# UNO_florist_automata_V1_10.net
KiCad netlist of a schematic drawn in EAGLE
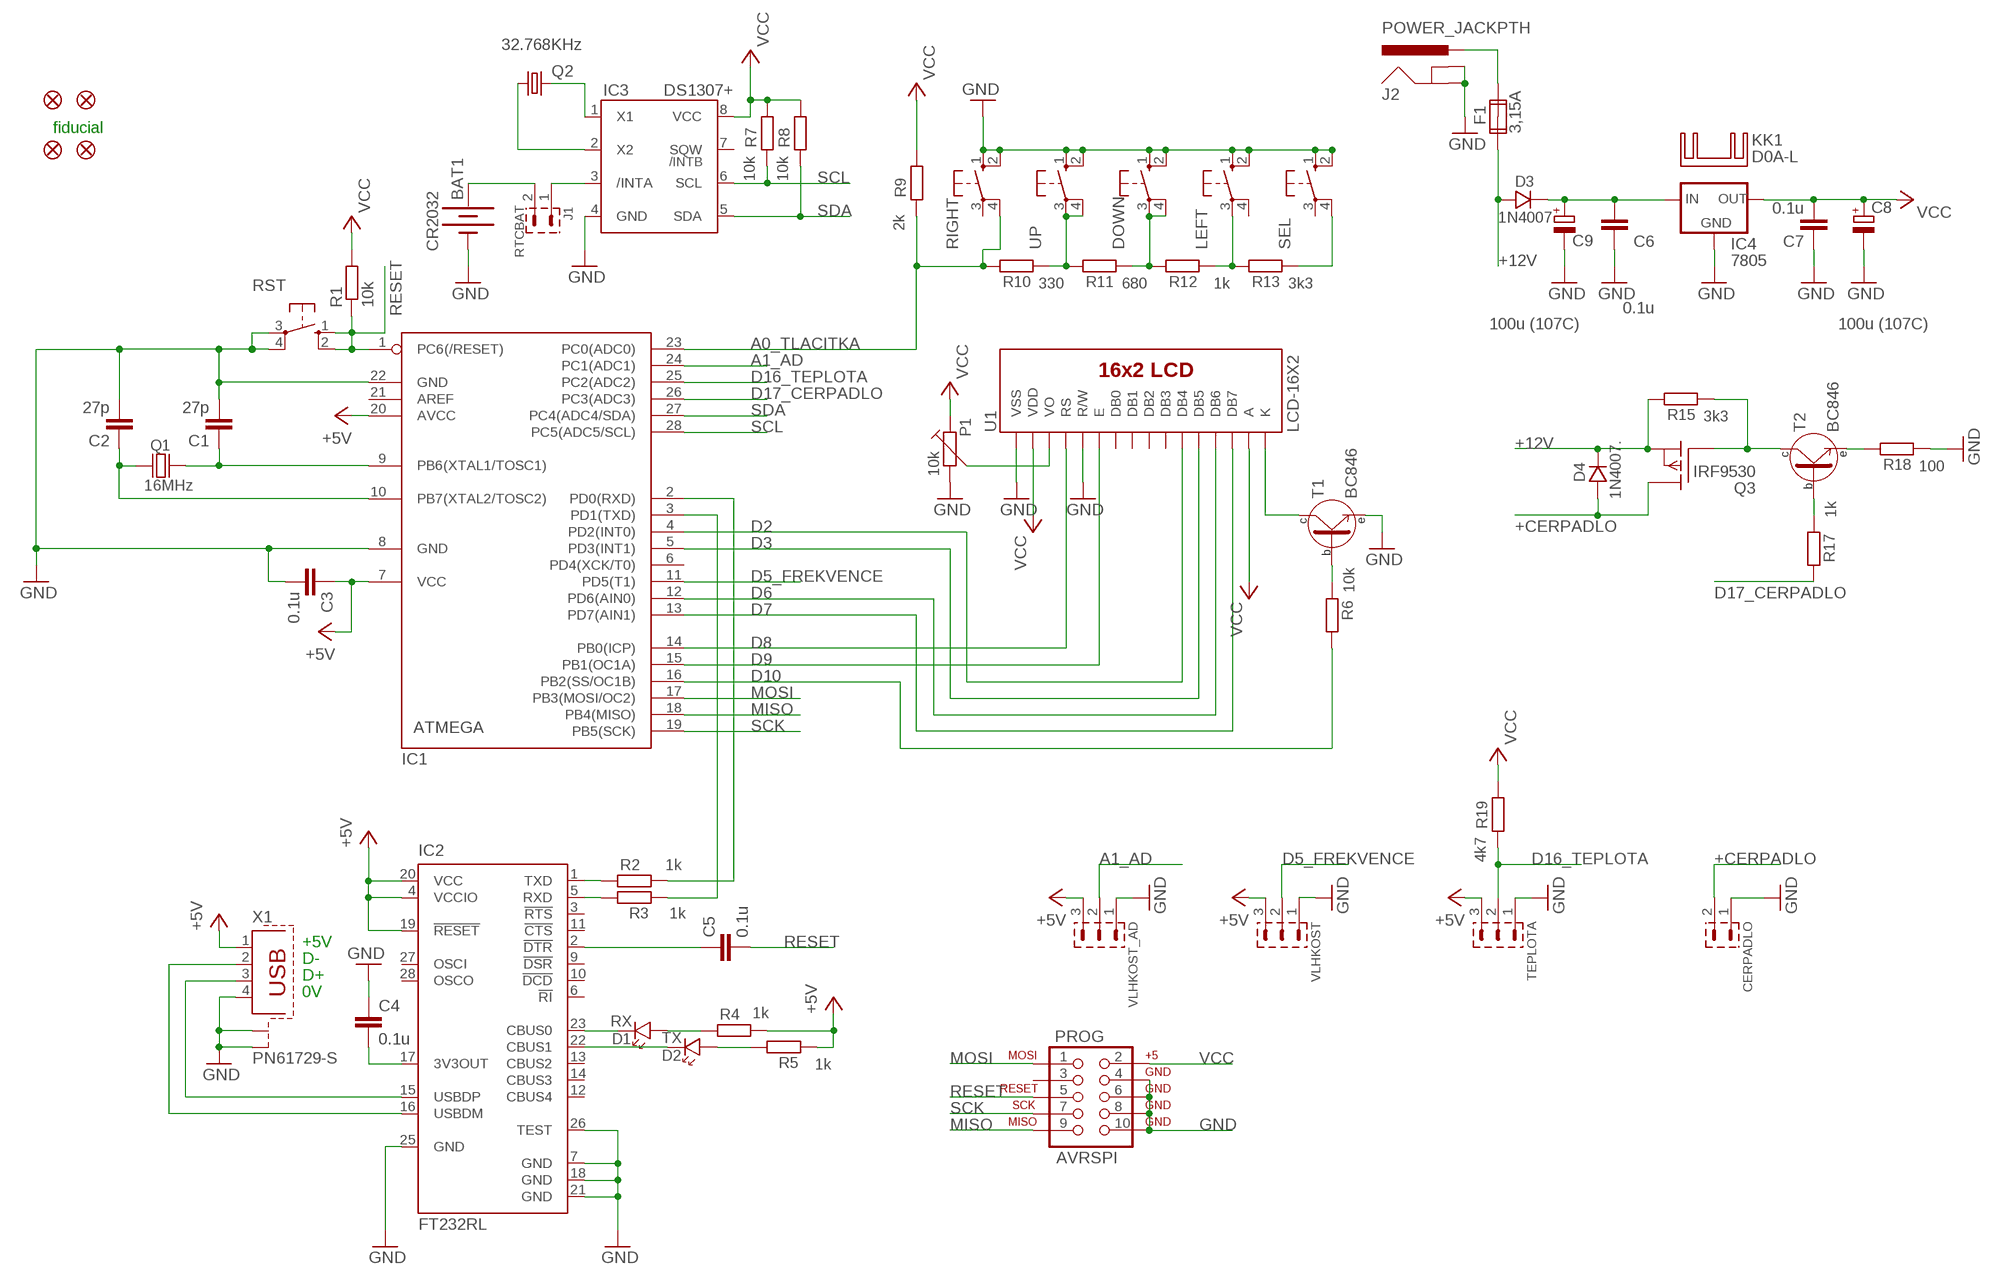
[diagram p0: schematic, sheet 1]

(export (version "E")
  (design (tool "Eeschema 10.0.6"))
  (components
    (comp (ref "BAT1")
      (value "CR2032")
      (footprint "eagle-import:BATTCOM_20MM_PTH")
      (libsource (lib "eagle-import") (part "BATTERY20PTH"))
    )
    (comp (ref "C1")
      (value "27p")
      (footprint "eagle-import:C1206")
      (libsource (lib "eagle-import") (part "C-EUC1206"))
    )
    (comp (ref "C2")
      (value "27p")
      (footprint "eagle-import:C1206")
      (libsource (lib "eagle-import") (part "C-EUC1206"))
    )
    (comp (ref "C3")
      (value "0.1u")
      (footprint "eagle-import:C1206")
      (libsource (lib "eagle-import") (part "C-EUC1206"))
    )
    (comp (ref "C4")
      (value "0.1u")
      (footprint "eagle-import:C1206")
      (libsource (lib "eagle-import") (part "C-EUC1206"))
    )
    (comp (ref "C5")
      (value "0.1u")
      (footprint "eagle-import:C1206")
      (libsource (lib "eagle-import") (part "C-EUC1206"))
    )
    (comp (ref "C6")
      (value "0.1u")
      (footprint "eagle-import:C1206")
      (libsource (lib "eagle-import") (part "C-EUC1206"))
    )
    (comp (ref "C7")
      (value "0.1u")
      (footprint "eagle-import:C1206")
      (libsource (lib "eagle-import") (part "C-EUC1206"))
    )
    (comp (ref "C8")
      (value "100u (107C)")
      (footprint "eagle-import:C_6032-28W")
      (libsource (lib "eagle-import") (part "CPOL-EUC/6032-28W"))
    )
    (comp (ref "C9")
      (value "100u (107C)")
      (footprint "eagle-import:C_6032-28W")
      (libsource (lib "eagle-import") (part "CPOL-EUC/6032-28W"))
    )
    (comp (ref "CERPADLO")
      (value "PSH02-02P")
      (footprint "eagle-import:PSH02-02P")
      (libsource (lib "eagle-import") (part "PSH02-02P"))
    )
    (comp (ref "D1")
      (value "RX")
      (footprint "eagle-import:P1206")
      (libsource (lib "eagle-import") (part "LED_1206"))
    )
    (comp (ref "D2")
      (value "TX")
      (footprint "eagle-import:P1206")
      (libsource (lib "eagle-import") (part "LED_1206"))
    )
    (comp (ref "D3")
      (value "1N4007.")
      (footprint "eagle-import:SM-1")
      (libsource (lib "eagle-import") (part "1N4007."))
    )
    (comp (ref "D4")
      (value "1N4007.")
      (footprint "eagle-import:SM-1")
      (libsource (lib "eagle-import") (part "1N4007."))
    )
    (comp (ref "DOWN")
      (value "10-XX")
      (footprint "eagle-import:B3F-10XX")
      (libsource (lib "eagle-import") (part "10-XX"))
    )
    (comp (ref "F1")
      (value "3,15A")
      (footprint "eagle-import:FUSE1")
      (libsource (lib "eagle-import") (part "FUSE2P"))
    )
    (comp (ref "FID1")
      (value "FIDUCIAL1.5X3")
      (footprint "eagle-import:FIDUCIAL-1.5X3")
      (libsource (lib "eagle-import") (part "FIDUCIAL1.5X3"))
    )
    (comp (ref "FID2")
      (value "FIDUCIAL1.5X3")
      (footprint "eagle-import:FIDUCIAL-1.5X3")
      (libsource (lib "eagle-import") (part "FIDUCIAL1.5X3"))
    )
    (comp (ref "FID3")
      (value "FIDUCIAL1.5X3")
      (footprint "eagle-import:FIDUCIAL-1.5X3")
      (libsource (lib "eagle-import") (part "FIDUCIAL1.5X3"))
    )
    (comp (ref "FID4")
      (value "FIDUCIAL1.5X3")
      (footprint "eagle-import:FIDUCIAL-1.5X3")
      (libsource (lib "eagle-import") (part "FIDUCIAL1.5X3"))
    )
    (comp (ref "IC1")
      (value "ATMEGA")
      (footprint "eagle-import:DIL28-3")
      (libsource (lib "eagle-import") (part "MEGA8-P"))
    )
    (comp (ref "IC2")
      (value "FT232RL")
      (footprint "eagle-import:SSOP28")
      (libsource (lib "eagle-import") (part "FT232RL"))
    )
    (comp (ref "IC3")
      (value "DS1307+")
      (footprint "eagle-import:SO08")
      (libsource (lib "eagle-import") (part "DS1337S+"))
    )
    (comp (ref "IC4")
      (value "7805")
      (footprint "eagle-import:78XXL")
      (libsource (lib "eagle-import") (part "78XXL"))
    )
    (comp (ref "J1")
      (value "RTCBAT")
      (footprint "eagle-import:S1G2_JUM")
      (libsource (lib "eagle-import") (part "S1G2_JUMP"))
    )
    (comp (ref "J2")
      (value "POWER_JACKPTH")
      (footprint "eagle-import:POWER_JACK_PTH")
      (libsource (lib "eagle-import") (part "POWER_JACKPTH"))
    )
    (comp (ref "KK1")
      (value "D0A-L")
      (footprint "eagle-import:D02A-L")
      (libsource (lib "eagle-import") (part "D0A-L"))
    )
    (comp (ref "LEFT")
      (value "10-XX")
      (footprint "eagle-import:B3F-10XX")
      (libsource (lib "eagle-import") (part "10-XX"))
    )
    (comp (ref "P1")
      (value "10k")
      (footprint "eagle-import:PT10V")
      (libsource (lib "eagle-import") (part "TRIMRPT10V"))
    )
    (comp (ref "PROG")
      (value "AVRSPI")
      (footprint "eagle-import:2X5-SHROUDED_LOCK")
      (libsource (lib "eagle-import") (part "AVR_SPI_PROG2LOCK"))
    )
    (comp (ref "Q1")
      (value "16MHz")
      (footprint "eagle-import:HC-49U")
      (libsource (lib "eagle-import") (part "Q_HC-49U"))
    )
    (comp (ref "Q2")
      (value "32.768KHz")
      (footprint "eagle-import:TC38H")
      (libsource (lib "eagle-import") (part "CRYSTALTC38H"))
    )
    (comp (ref "Q3")
      (value "IRF9530")
      (footprint "eagle-import:TO220")
      (libsource (lib "eagle-import") (part "IRF9530"))
    )
    (comp (ref "R1")
      (value "10k")
      (footprint "eagle-import:M1206")
      (libsource (lib "eagle-import") (part "R-EU_M1206"))
    )
    (comp (ref "R2")
      (value "1k")
      (footprint "eagle-import:M1206")
      (libsource (lib "eagle-import") (part "R-EU_M1206"))
    )
    (comp (ref "R3")
      (value "1k")
      (footprint "eagle-import:M1206")
      (libsource (lib "eagle-import") (part "R-EU_M1206"))
    )
    (comp (ref "R4")
      (value "1k")
      (footprint "eagle-import:M1206")
      (libsource (lib "eagle-import") (part "R-EU_M1206"))
    )
    (comp (ref "R5")
      (value "1k")
      (footprint "eagle-import:M1206")
      (libsource (lib "eagle-import") (part "R-EU_M1206"))
    )
    (comp (ref "R6")
      (value "10k")
      (footprint "eagle-import:M1206")
      (libsource (lib "eagle-import") (part "R-EU_M1206"))
    )
    (comp (ref "R7")
      (value "10k")
      (footprint "eagle-import:M1206")
      (libsource (lib "eagle-import") (part "R-EU_M1206"))
    )
    (comp (ref "R8")
      (value "10k")
      (footprint "eagle-import:M1206")
      (libsource (lib "eagle-import") (part "R-EU_M1206"))
    )
    (comp (ref "R9")
      (value "2k")
      (footprint "eagle-import:M1206")
      (libsource (lib "eagle-import") (part "R-EU_M1206"))
    )
    (comp (ref "R10")
      (value "330")
      (footprint "eagle-import:M1206")
      (libsource (lib "eagle-import") (part "R-EU_M1206"))
    )
    (comp (ref "R11")
      (value "680")
      (footprint "eagle-import:M1206")
      (libsource (lib "eagle-import") (part "R-EU_M1206"))
    )
    (comp (ref "R12")
      (value "1k")
      (footprint "eagle-import:M1206")
      (libsource (lib "eagle-import") (part "R-EU_M1206"))
    )
    (comp (ref "R13")
      (value "3k3")
      (footprint "eagle-import:M1206")
      (libsource (lib "eagle-import") (part "R-EU_M1206"))
    )
    (comp (ref "R15")
      (value "3k3")
      (footprint "eagle-import:M1206")
      (libsource (lib "eagle-import") (part "R-EU_M1206"))
    )
    (comp (ref "R17")
      (value "1k")
      (footprint "eagle-import:M1206")
      (libsource (lib "eagle-import") (part "R-EU_M1206"))
    )
    (comp (ref "R18")
      (value "100")
      (footprint "eagle-import:M1206")
      (libsource (lib "eagle-import") (part "R-EU_M1206"))
    )
    (comp (ref "R19")
      (value "4k7")
      (footprint "eagle-import:M1206")
      (libsource (lib "eagle-import") (part "R-EU_M1206"))
    )
    (comp (ref "RIGHT")
      (value "10-XX")
      (footprint "eagle-import:B3F-10XX")
      (libsource (lib "eagle-import") (part "10-XX"))
    )
    (comp (ref "RST")
      (value "10-XX")
      (footprint "eagle-import:B3F-10XX")
      (libsource (lib "eagle-import") (part "10-XX"))
    )
    (comp (ref "SEL")
      (value "10-XX")
      (footprint "eagle-import:B3F-10XX")
      (libsource (lib "eagle-import") (part "10-XX"))
    )
    (comp (ref "T1")
      (value "BC846")
      (footprint "eagle-import:SOT-23")
      (libsource (lib "eagle-import") (part "BC846"))
    )
    (comp (ref "T2")
      (value "BC846")
      (footprint "eagle-import:SOT-23")
      (libsource (lib "eagle-import") (part "BC846"))
    )
    (comp (ref "TEPLOTA")
      (value "PSH02-03P")
      (footprint "eagle-import:PSH02-03P")
      (libsource (lib "eagle-import") (part "PSH02-03P"))
    )
    (comp (ref "U1")
      (value "LCD-16X2")
      (footprint "eagle-import:LCD-16X2_NOSILK")
      (libsource (lib "eagle-import") (part "LCD-16X2NOSILK"))
    )
    (comp (ref "UP")
      (value "10-XX")
      (footprint "eagle-import:B3F-10XX")
      (libsource (lib "eagle-import") (part "10-XX"))
    )
    (comp (ref "VLHKOST")
      (value "PSH02-03P")
      (footprint "eagle-import:PSH02-03P")
      (libsource (lib "eagle-import") (part "PSH02-03P"))
    )
    (comp (ref "VLHKOST_AD")
      (value "PSH02-03P")
      (footprint "eagle-import:PSH02-03P")
      (libsource (lib "eagle-import") (part "PSH02-03P"))
    )
    (comp (ref "X1")
      (value "PN61729-S")
      (footprint "eagle-import:PN61729-S")
      (libsource (lib "eagle-import") (part "PN61729-S"))
    )
  )
  (nets
    (net (code "1") (name "+5V") (class "Default")
      (node (ref "C3") (pin "1") (pinfunction "1_1") (pintype "passive"))
      (node (ref "C7") (pin "2") (pinfunction "2_2") (pintype "passive"))
      (node (ref "C8") (pin "+") (pinfunction "+_+") (pintype "passive"))
      (node (ref "IC1") (pin "20") (pinfunction "AVCC_20") (pintype "power_in"))
      (node (ref "IC1") (pin "7") (pinfunction "VCC_7") (pintype "power_in"))
      (node (ref "IC2") (pin "19") (pinfunction "~{RESET}_19") (pintype "input"))
      (node (ref "IC2") (pin "20") (pinfunction "VCC_20") (pintype "power_in"))
      (node (ref "IC2") (pin "4") (pinfunction "VCCIO_4") (pintype "power_in"))
      (node (ref "IC3") (pin "8") (pinfunction "VCC_8") (pintype "power_in"))
      (node (ref "IC4") (pin "OUT") (pinfunction "OUT_OUT") (pintype "passive"))
      (node (ref "P1") (pin "1") (pinfunction "1_1") (pintype "passive"))
      (node (ref "PROG") (pin "2") (pinfunction "2_2") (pintype "passive"))
      (node (ref "R1") (pin "2") (pinfunction "2_2") (pintype "passive"))
      (node (ref "R19") (pin "2") (pinfunction "2_2") (pintype "passive"))
      (node (ref "R4") (pin "2") (pinfunction "2_2") (pintype "passive"))
      (node (ref "R5") (pin "1") (pinfunction "1_1") (pintype "passive"))
      (node (ref "R7") (pin "2") (pinfunction "2_2") (pintype "passive"))
      (node (ref "R8") (pin "2") (pinfunction "2_2") (pintype "passive"))
      (node (ref "R9") (pin "2") (pinfunction "2_2") (pintype "passive"))
      (node (ref "TEPLOTA") (pin "3") (pinfunction "3_3") (pintype "passive"))
      (node (ref "U1") (pin "15") (pinfunction "A_15") (pintype "power_in"))
      (node (ref "U1") (pin "2") (pinfunction "VDD_2") (pintype "power_in"))
      (node (ref "VLHKOST") (pin "3") (pinfunction "3_3") (pintype "passive"))
      (node (ref "VLHKOST_AD") (pin "3") (pinfunction "3_3") (pintype "passive"))
      (node (ref "X1") (pin "1") (pinfunction "1_1") (pintype "passive"))
    )
    (net (code "2") (name "/+12V") (class "Default")
      (node (ref "D3") (pin "A") (pinfunction "A_A") (pintype "passive"))
      (node (ref "D4") (pin "K") (pinfunction "K_K") (pintype "passive"))
      (node (ref "F1") (pin "1A") (pinfunction "1A_1A") (pintype "passive"))
      (node (ref "Q3") (pin "3") (pinfunction "S_3") (pintype "passive"))
      (node (ref "R15") (pin "2") (pinfunction "2_2") (pintype "passive"))
    )
    (net (code "3") (name "/+CERPADLO") (class "Default")
      (node (ref "CERPADLO") (pin "2") (pinfunction "2_2") (pintype "passive"))
      (node (ref "D4") (pin "A") (pinfunction "A_A") (pintype "passive"))
      (node (ref "Q3") (pin "2") (pinfunction "D_2") (pintype "passive"))
    )
    (net (code "4") (name "/A0_TLACITKA") (class "Default")
      (node (ref "IC1") (pin "23") (pinfunction "PC0(ADC0)_23") (pintype "bidirectional"))
      (node (ref "R10") (pin "2") (pinfunction "2_2") (pintype "passive"))
      (node (ref "R9") (pin "1") (pinfunction "1_1") (pintype "passive"))
      (node (ref "RIGHT") (pin "4") (pinfunction "P1_4") (pintype "passive"))
    )
    (net (code "5") (name "/A1_AD") (class "Default")
      (node (ref "IC1") (pin "24") (pinfunction "PC1(ADC1)_24") (pintype "bidirectional"))
      (node (ref "VLHKOST_AD") (pin "2") (pinfunction "2_2") (pintype "passive"))
    )
    (net (code "6") (name "/D2") (class "Default")
      (node (ref "IC1") (pin "4") (pinfunction "PD2(INT0)_4") (pintype "bidirectional"))
      (node (ref "U1") (pin "11") (pinfunction "DB4_11") (pintype "bidirectional"))
    )
    (net (code "7") (name "/D3") (class "Default")
      (node (ref "IC1") (pin "5") (pinfunction "PD3(INT1)_5") (pintype "bidirectional"))
      (node (ref "U1") (pin "12") (pinfunction "DB5_12") (pintype "bidirectional"))
    )
    (net (code "8") (name "/D5_FREKVENCE") (class "Default")
      (node (ref "IC1") (pin "11") (pinfunction "PD5(T1)_11") (pintype "bidirectional"))
      (node (ref "VLHKOST") (pin "2") (pinfunction "2_2") (pintype "passive"))
    )
    (net (code "9") (name "/D6") (class "Default")
      (node (ref "IC1") (pin "12") (pinfunction "PD6(AIN0)_12") (pintype "bidirectional"))
      (node (ref "U1") (pin "13") (pinfunction "DB6_13") (pintype "bidirectional"))
    )
    (net (code "10") (name "/D7") (class "Default")
      (node (ref "IC1") (pin "13") (pinfunction "PD7(AIN1)_13") (pintype "bidirectional"))
      (node (ref "U1") (pin "14") (pinfunction "DB7_14") (pintype "bidirectional"))
    )
    (net (code "11") (name "/D8") (class "Default")
      (node (ref "IC1") (pin "14") (pinfunction "PB0(ICP)_14") (pintype "bidirectional"))
      (node (ref "U1") (pin "4") (pinfunction "RS_4") (pintype "input"))
    )
    (net (code "12") (name "/D9") (class "Default")
      (node (ref "IC1") (pin "15") (pinfunction "PB1(OC1A)_15") (pintype "bidirectional"))
      (node (ref "U1") (pin "6") (pinfunction "E_6") (pintype "input"))
    )
    (net (code "13") (name "/D10") (class "Default")
      (node (ref "IC1") (pin "16") (pinfunction "PB2(SS/OC1B)_16") (pintype "bidirectional"))
      (node (ref "R6") (pin "2") (pinfunction "2_2") (pintype "passive"))
    )
    (net (code "14") (name "/D16_TEPLOTA") (class "Default")
      (node (ref "IC1") (pin "25") (pinfunction "PC2(ADC2)_25") (pintype "bidirectional"))
      (node (ref "R19") (pin "1") (pinfunction "1_1") (pintype "passive"))
      (node (ref "TEPLOTA") (pin "2") (pinfunction "2_2") (pintype "passive"))
    )
    (net (code "15") (name "/D17_CERPADLO") (class "Default")
      (node (ref "IC1") (pin "26") (pinfunction "PC3(ADC3)_26") (pintype "bidirectional"))
      (node (ref "R17") (pin "2") (pinfunction "2_2") (pintype "passive"))
    )
    (net (code "16") (name "/MISO") (class "Default")
      (node (ref "IC1") (pin "18") (pinfunction "PB4(MISO)_18") (pintype "bidirectional"))
      (node (ref "PROG") (pin "9") (pinfunction "9_9") (pintype "passive"))
    )
    (net (code "17") (name "/MOSI") (class "Default")
      (node (ref "IC1") (pin "17") (pinfunction "PB3(MOSI/OC2)_17") (pintype "bidirectional"))
      (node (ref "PROG") (pin "1") (pinfunction "1_1") (pintype "passive"))
    )
    (net (code "18") (name "/RESET") (class "Default")
      (node (ref "C5") (pin "2") (pinfunction "2_2") (pintype "passive"))
      (node (ref "IC1") (pin "1") (pinfunction "PC6(/RESET)_1") (pintype "bidirectional"))
      (node (ref "PROG") (pin "5") (pinfunction "5_5") (pintype "passive"))
      (node (ref "R1") (pin "1") (pinfunction "1_1") (pintype "passive"))
      (node (ref "RST") (pin "1") (pinfunction "S_1") (pintype "passive"))
      (node (ref "RST") (pin "2") (pinfunction "S1_2") (pintype "passive"))
    )
    (net (code "19") (name "/SCK") (class "Default")
      (node (ref "IC1") (pin "19") (pinfunction "PB5(SCK)_19") (pintype "bidirectional"))
      (node (ref "PROG") (pin "7") (pinfunction "7_7") (pintype "passive"))
    )
    (net (code "20") (name "/SCL") (class "Default")
      (node (ref "IC1") (pin "28") (pinfunction "PC5(ADC5/SCL)_28") (pintype "bidirectional"))
      (node (ref "IC3") (pin "6") (pinfunction "SCL_6") (pintype "bidirectional"))
      (node (ref "R7") (pin "1") (pinfunction "1_1") (pintype "passive"))
    )
    (net (code "21") (name "/SDA") (class "Default")
      (node (ref "IC1") (pin "27") (pinfunction "PC4(ADC4/SDA)_27") (pintype "bidirectional"))
      (node (ref "IC3") (pin "5") (pinfunction "SDA_5") (pintype "bidirectional"))
      (node (ref "R8") (pin "1") (pinfunction "1_1") (pintype "passive"))
    )
    (net (code "22") (name "GND") (class "Default")
      (node (ref "BAT1") (pin "2") (pinfunction "-_2") (pintype "power_in"))
      (node (ref "C1") (pin "2") (pinfunction "2_2") (pintype "passive"))
      (node (ref "C2") (pin "2") (pinfunction "2_2") (pintype "passive"))
      (node (ref "C3") (pin "2") (pinfunction "2_2") (pintype "passive"))
      (node (ref "C4") (pin "1") (pinfunction "1_1") (pintype "passive"))
      (node (ref "C6") (pin "1") (pinfunction "1_1") (pintype "passive"))
      (node (ref "C7") (pin "1") (pinfunction "1_1") (pintype "passive"))
      (node (ref "C8") (pin "-") (pinfunction "-_-") (pintype "passive"))
      (node (ref "C9") (pin "-") (pinfunction "-_-") (pintype "passive"))
      (node (ref "CERPADLO") (pin "1") (pinfunction "1_1") (pintype "passive"))
      (node (ref "DOWN") (pin "1") (pinfunction "S_1") (pintype "passive"))
      (node (ref "DOWN") (pin "2") (pinfunction "S1_2") (pintype "passive"))
      (node (ref "IC1") (pin "22") (pinfunction "GND_22") (pintype "power_in"))
      (node (ref "IC1") (pin "8") (pinfunction "GND_8") (pintype "power_in"))
      (node (ref "IC2") (pin "18") (pinfunction "GND_18") (pintype "power_in"))
      (node (ref "IC2") (pin "21") (pinfunction "GND_21") (pintype "power_in"))
      (node (ref "IC2") (pin "25") (pinfunction "GND_25") (pintype "power_in"))
      (node (ref "IC2") (pin "26") (pinfunction "TEST_26") (pintype "input"))
      (node (ref "IC2") (pin "7") (pinfunction "GND_7") (pintype "power_in"))
      (node (ref "IC3") (pin "4") (pinfunction "GND_4") (pintype "power_in"))
      (node (ref "IC4") (pin "GND") (pinfunction "GND_GND") (pintype "input"))
      (node (ref "J2") (pin "GND") (pinfunction "GND_GND") (pintype "bidirectional"))
      (node (ref "J2") (pin "GNDBREAK") (pinfunction "GNDBREAK_GNDBREAK") (pintype "bidirectional"))
      (node (ref "LEFT") (pin "1") (pinfunction "S_1") (pintype "passive"))
      (node (ref "LEFT") (pin "2") (pinfunction "S1_2") (pintype "passive"))
      (node (ref "P1") (pin "2") (pinfunction "2_2") (pintype "passive"))
      (node (ref "PROG") (pin "10") (pinfunction "10_10") (pintype "passive"))
      (node (ref "PROG") (pin "4") (pinfunction "4_4") (pintype "passive"))
      (node (ref "PROG") (pin "6") (pinfunction "6_6") (pintype "passive"))
      (node (ref "PROG") (pin "8") (pinfunction "8_8") (pintype "passive"))
      (node (ref "R18") (pin "1") (pinfunction "1_1") (pintype "passive"))
      (node (ref "RIGHT") (pin "1") (pinfunction "S_1") (pintype "passive"))
      (node (ref "RIGHT") (pin "2") (pinfunction "S1_2") (pintype "passive"))
      (node (ref "RST") (pin "3") (pinfunction "P_3") (pintype "passive"))
      (node (ref "RST") (pin "4") (pinfunction "P1_4") (pintype "passive"))
      (node (ref "SEL") (pin "1") (pinfunction "S_1") (pintype "passive"))
      (node (ref "SEL") (pin "2") (pinfunction "S1_2") (pintype "passive"))
      (node (ref "T1") (pin "2") (pinfunction "E_2") (pintype "passive"))
      (node (ref "TEPLOTA") (pin "1") (pinfunction "1_1") (pintype "passive"))
      (node (ref "U1") (pin "1") (pinfunction "VSS_1") (pintype "power_in"))
      (node (ref "U1") (pin "5") (pinfunction "R/W_5") (pintype "input"))
      (node (ref "UP") (pin "1") (pinfunction "S_1") (pintype "passive"))
      (node (ref "UP") (pin "2") (pinfunction "S1_2") (pintype "passive"))
      (node (ref "VLHKOST") (pin "1") (pinfunction "1_1") (pintype "passive"))
      (node (ref "VLHKOST_AD") (pin "1") (pinfunction "1_1") (pintype "passive"))
      (node (ref "X1") (pin "4") (pinfunction "4_4") (pintype "passive"))
      (node (ref "X1") (pin "S1") (pinfunction "S1_S1") (pintype "passive"))
      (node (ref "X1") (pin "S2") (pinfunction "S2_S2") (pintype "passive"))
    )
    (net (code "23") (name "Net-(BAT1-+)") (class "Default")
      (node (ref "BAT1") (pin "1") (pinfunction "+_1") (pintype "power_in"))
      (node (ref "J1") (pin "2") (pinfunction "2_2") (pintype "passive"))
    )
    (net (code "24") (name "Net-(C6-Pad2)") (class "Default")
      (node (ref "C6") (pin "2") (pinfunction "2_2") (pintype "passive"))
      (node (ref "C9") (pin "+") (pinfunction "+_+") (pintype "passive"))
      (node (ref "D3") (pin "K") (pinfunction "K_K") (pintype "passive"))
      (node (ref "IC4") (pin "IN") (pinfunction "IN_IN") (pintype "input"))
    )
    (net (code "25") (name "Net-(D1-PadA)") (class "Default")
      (node (ref "D1") (pin "A") (pinfunction "A_A") (pintype "passive"))
      (node (ref "R4") (pin "1") (pinfunction "1_1") (pintype "passive"))
    )
    (net (code "26") (name "Net-(D2-PadA)") (class "Default")
      (node (ref "D2") (pin "A") (pinfunction "A_A") (pintype "passive"))
      (node (ref "R5") (pin "2") (pinfunction "2_2") (pintype "passive"))
    )
    (net (code "27") (name "Net-(DOWN-P)") (class "Default")
      (node (ref "DOWN") (pin "3") (pinfunction "P_3") (pintype "passive"))
      (node (ref "DOWN") (pin "4") (pinfunction "P1_4") (pintype "passive"))
      (node (ref "R11") (pin "1") (pinfunction "1_1") (pintype "passive"))
      (node (ref "R12") (pin "2") (pinfunction "2_2") (pintype "passive"))
    )
    (net (code "28") (name "Net-(F1-Pad2A)") (class "Default")
      (node (ref "F1") (pin "2A") (pinfunction "2A_2A") (pintype "passive"))
      (node (ref "J2") (pin "PWR") (pinfunction "PWR_PWR") (pintype "bidirectional"))
    )
    (net (code "29") (name "Net-(IC1-PB6(XTAL1{slash}TOSC1))") (class "Default")
      (node (ref "C1") (pin "1") (pinfunction "1_1") (pintype "passive"))
      (node (ref "IC1") (pin "9") (pinfunction "PB6(XTAL1/TOSC1)_9") (pintype "bidirectional"))
      (node (ref "Q1") (pin "2") (pinfunction "2_2") (pintype "passive"))
    )
    (net (code "30") (name "Net-(IC1-PB7(XTAL2{slash}TOSC2))") (class "Default")
      (node (ref "C2") (pin "1") (pinfunction "1_1") (pintype "passive"))
      (node (ref "IC1") (pin "10") (pinfunction "PB7(XTAL2/TOSC2)_10") (pintype "bidirectional"))
      (node (ref "Q1") (pin "1") (pinfunction "1_1") (pintype "passive"))
    )
    (net (code "31") (name "Net-(IC1-PD0(RXD))") (class "Default")
      (node (ref "IC1") (pin "2") (pinfunction "PD0(RXD)_2") (pintype "bidirectional"))
      (node (ref "R2") (pin "2") (pinfunction "2_2") (pintype "passive"))
    )
    (net (code "32") (name "Net-(IC1-PD1(TXD))") (class "Default")
      (node (ref "IC1") (pin "3") (pinfunction "PD1(TXD)_3") (pintype "bidirectional"))
      (node (ref "R3") (pin "1") (pinfunction "1_1") (pintype "passive"))
    )
    (net (code "33") (name "Net-(IC2-3V3OUT)") (class "Default")
      (node (ref "C4") (pin "2") (pinfunction "2_2") (pintype "passive"))
      (node (ref "IC2") (pin "17") (pinfunction "3V3OUT_17") (pintype "output"))
    )
    (net (code "34") (name "Net-(IC2-CBUS0)") (class "Default")
      (node (ref "D1") (pin "K") (pinfunction "K_K") (pintype "passive"))
      (node (ref "IC2") (pin "23") (pinfunction "CBUS0_23") (pintype "bidirectional"))
    )
    (net (code "35") (name "Net-(IC2-CBUS1)") (class "Default")
      (node (ref "D2") (pin "K") (pinfunction "K_K") (pintype "passive"))
      (node (ref "IC2") (pin "22") (pinfunction "CBUS1_22") (pintype "bidirectional"))
    )
    (net (code "36") (name "Net-(IC2-RXD)") (class "Default")
      (node (ref "IC2") (pin "5") (pinfunction "RXD_5") (pintype "input"))
      (node (ref "R3") (pin "2") (pinfunction "2_2") (pintype "passive"))
    )
    (net (code "37") (name "Net-(IC2-TXD)") (class "Default")
      (node (ref "IC2") (pin "1") (pinfunction "TXD_1") (pintype "output"))
      (node (ref "R2") (pin "1") (pinfunction "1_1") (pintype "passive"))
    )
    (net (code "38") (name "Net-(IC2-USBDM)") (class "Default")
      (node (ref "IC2") (pin "16") (pinfunction "USBDM_16") (pintype "bidirectional"))
      (node (ref "X1") (pin "2") (pinfunction "2_2") (pintype "passive"))
    )
    (net (code "39") (name "Net-(IC2-USBDP)") (class "Default")
      (node (ref "IC2") (pin "15") (pinfunction "USBDP_15") (pintype "bidirectional"))
      (node (ref "X1") (pin "3") (pinfunction "3_3") (pintype "passive"))
    )
    (net (code "40") (name "Net-(IC2-~{DTR})") (class "Default")
      (node (ref "C5") (pin "1") (pinfunction "1_1") (pintype "passive"))
      (node (ref "IC2") (pin "2") (pinfunction "~{DTR}_2") (pintype "output"))
    )
    (net (code "41") (name "Net-(IC3-X1)") (class "Default")
      (node (ref "IC3") (pin "1") (pinfunction "X1_1") (pintype "bidirectional"))
      (node (ref "Q2") (pin "2") (pinfunction "2_2") (pintype "passive"))
    )
    (net (code "42") (name "Net-(IC3-X2)") (class "Default")
      (node (ref "IC3") (pin "2") (pinfunction "X2_2") (pintype "bidirectional"))
      (node (ref "Q2") (pin "1") (pinfunction "1_1") (pintype "passive"))
    )
    (net (code "43") (name "Net-(IC3-{slash}INTA)") (class "Default")
      (node (ref "IC3") (pin "3") (pinfunction "/INTA_3") (pintype "bidirectional"))
      (node (ref "J1") (pin "1") (pinfunction "1_1") (pintype "passive"))
    )
    (net (code "44") (name "Net-(LEFT-P)") (class "Default")
      (node (ref "LEFT") (pin "3") (pinfunction "P_3") (pintype "passive"))
      (node (ref "R12") (pin "1") (pinfunction "1_1") (pintype "passive"))
      (node (ref "R13") (pin "2") (pinfunction "2_2") (pintype "passive"))
    )
    (net (code "45") (name "Net-(Q3-G)") (class "Default")
      (node (ref "Q3") (pin "1") (pinfunction "G_1") (pintype "passive"))
      (node (ref "R15") (pin "1") (pinfunction "1_1") (pintype "passive"))
      (node (ref "T2") (pin "3") (pinfunction "C_3") (pintype "passive"))
    )
    (net (code "46") (name "Net-(SEL-P1)") (class "Default")
      (node (ref "R13") (pin "1") (pinfunction "1_1") (pintype "passive"))
      (node (ref "SEL") (pin "4") (pinfunction "P1_4") (pintype "passive"))
    )
    (net (code "47") (name "Net-(T1-B)") (class "Default")
      (node (ref "R6") (pin "1") (pinfunction "1_1") (pintype "passive"))
      (node (ref "T1") (pin "1") (pinfunction "B_1") (pintype "passive"))
    )
    (net (code "48") (name "Net-(T1-C)") (class "Default")
      (node (ref "T1") (pin "3") (pinfunction "C_3") (pintype "passive"))
      (node (ref "U1") (pin "16") (pinfunction "K_16") (pintype "power_in"))
    )
    (net (code "49") (name "Net-(T2-B)") (class "Default")
      (node (ref "R17") (pin "1") (pinfunction "1_1") (pintype "passive"))
      (node (ref "T2") (pin "1") (pinfunction "B_1") (pintype "passive"))
    )
    (net (code "50") (name "Net-(T2-E)") (class "Default")
      (node (ref "R18") (pin "2") (pinfunction "2_2") (pintype "passive"))
      (node (ref "T2") (pin "2") (pinfunction "E_2") (pintype "passive"))
    )
    (net (code "51") (name "Net-(U1-VO)") (class "Default")
      (node (ref "P1") (pin "3") (pinfunction "3_3") (pintype "passive"))
      (node (ref "U1") (pin "3") (pinfunction "VO_3") (pintype "bidirectional"))
    )
    (net (code "52") (name "Net-(UP-P)") (class "Default")
      (node (ref "R10") (pin "1") (pinfunction "1_1") (pintype "passive"))
      (node (ref "R11") (pin "2") (pinfunction "2_2") (pintype "passive"))
      (node (ref "UP") (pin "3") (pinfunction "P_3") (pintype "passive"))
      (node (ref "UP") (pin "4") (pinfunction "P1_4") (pintype "passive"))
    )
    (net (code "53") (name "unconnected-(F1-Pad1B)") (class "Default")
      (node (ref "F1") (pin "1B") (pinfunction "1B_1B") (pintype "passive"))
    )
    (net (code "54") (name "unconnected-(F1-Pad2B)") (class "Default")
      (node (ref "F1") (pin "2B") (pinfunction "2B_2B") (pintype "passive"))
    )
    (net (code "55") (name "unconnected-(IC1-AREF-Pad21)") (class "Default")
      (node (ref "IC1") (pin "21") (pinfunction "AREF_21") (pintype "passive"))
    )
    (net (code "56") (name "unconnected-(IC1-PD4(XCK{slash}T0)-Pad6)") (class "Default")
      (node (ref "IC1") (pin "6") (pinfunction "PD4(XCK/T0)_6") (pintype "bidirectional"))
    )
    (net (code "57") (name "unconnected-(IC2-CBUS2-Pad13)") (class "Default")
      (node (ref "IC2") (pin "13") (pinfunction "CBUS2_13") (pintype "bidirectional"))
    )
    (net (code "58") (name "unconnected-(IC2-CBUS3-Pad14)") (class "Default")
      (node (ref "IC2") (pin "14") (pinfunction "CBUS3_14") (pintype "bidirectional"))
    )
    (net (code "59") (name "unconnected-(IC2-CBUS4-Pad12)") (class "Default")
      (node (ref "IC2") (pin "12") (pinfunction "CBUS4_12") (pintype "bidirectional"))
    )
    (net (code "60") (name "unconnected-(IC2-OSCI-Pad27)") (class "Default")
      (node (ref "IC2") (pin "27") (pinfunction "OSCI_27") (pintype "input"))
    )
    (net (code "61") (name "unconnected-(IC2-OSCO-Pad28)") (class "Default")
      (node (ref "IC2") (pin "28") (pinfunction "OSCO_28") (pintype "output"))
    )
    (net (code "62") (name "unconnected-(IC2-~{CTS}-Pad11)") (class "Default")
      (node (ref "IC2") (pin "11") (pinfunction "~{CTS}_11") (pintype "input"))
    )
    (net (code "63") (name "unconnected-(IC2-~{DCD}-Pad10)") (class "Default")
      (node (ref "IC2") (pin "10") (pinfunction "~{DCD}_10") (pintype "input"))
    )
    (net (code "64") (name "unconnected-(IC2-~{DSR}-Pad9)") (class "Default")
      (node (ref "IC2") (pin "9") (pinfunction "~{DSR}_9") (pintype "input"))
    )
    (net (code "65") (name "unconnected-(IC2-~{RI}-Pad6)") (class "Default")
      (node (ref "IC2") (pin "6") (pinfunction "~{RI}_6") (pintype "input"))
    )
    (net (code "66") (name "unconnected-(IC2-~{RTS}-Pad3)") (class "Default")
      (node (ref "IC2") (pin "3") (pinfunction "~{RTS}_3") (pintype "output"))
    )
    (net (code "67") (name "unconnected-(IC3-SQW-Pad7)") (class "Default")
      (node (ref "IC3") (pin "7") (pinfunction "SQW_7") (pintype "bidirectional"))
    )
    (net (code "68") (name "unconnected-(LEFT-P1-Pad4)") (class "Default")
      (node (ref "LEFT") (pin "4") (pinfunction "P1_4") (pintype "passive"))
    )
    (net (code "69") (name "unconnected-(PROG-Pad3)") (class "Default")
      (node (ref "PROG") (pin "3") (pinfunction "3_3") (pintype "passive"))
    )
    (net (code "70") (name "unconnected-(RIGHT-P-Pad3)") (class "Default")
      (node (ref "RIGHT") (pin "3") (pinfunction "P_3") (pintype "passive"))
    )
    (net (code "71") (name "unconnected-(SEL-P-Pad3)") (class "Default")
      (node (ref "SEL") (pin "3") (pinfunction "P_3") (pintype "passive"))
    )
    (net (code "72") (name "unconnected-(U1-DB0-Pad7)") (class "Default")
      (node (ref "U1") (pin "7") (pinfunction "DB0_7") (pintype "bidirectional"))
    )
    (net (code "73") (name "unconnected-(U1-DB1-Pad8)") (class "Default")
      (node (ref "U1") (pin "8") (pinfunction "DB1_8") (pintype "bidirectional"))
    )
    (net (code "74") (name "unconnected-(U1-DB2-Pad9)") (class "Default")
      (node (ref "U1") (pin "9") (pinfunction "DB2_9") (pintype "bidirectional"))
    )
    (net (code "75") (name "unconnected-(U1-DB3-Pad10)") (class "Default")
      (node (ref "U1") (pin "10") (pinfunction "DB3_10") (pintype "bidirectional"))
    )
  )
)
